# kirschmann-adsr.net
KiCad netlist of a schematic drawn in EAGLE
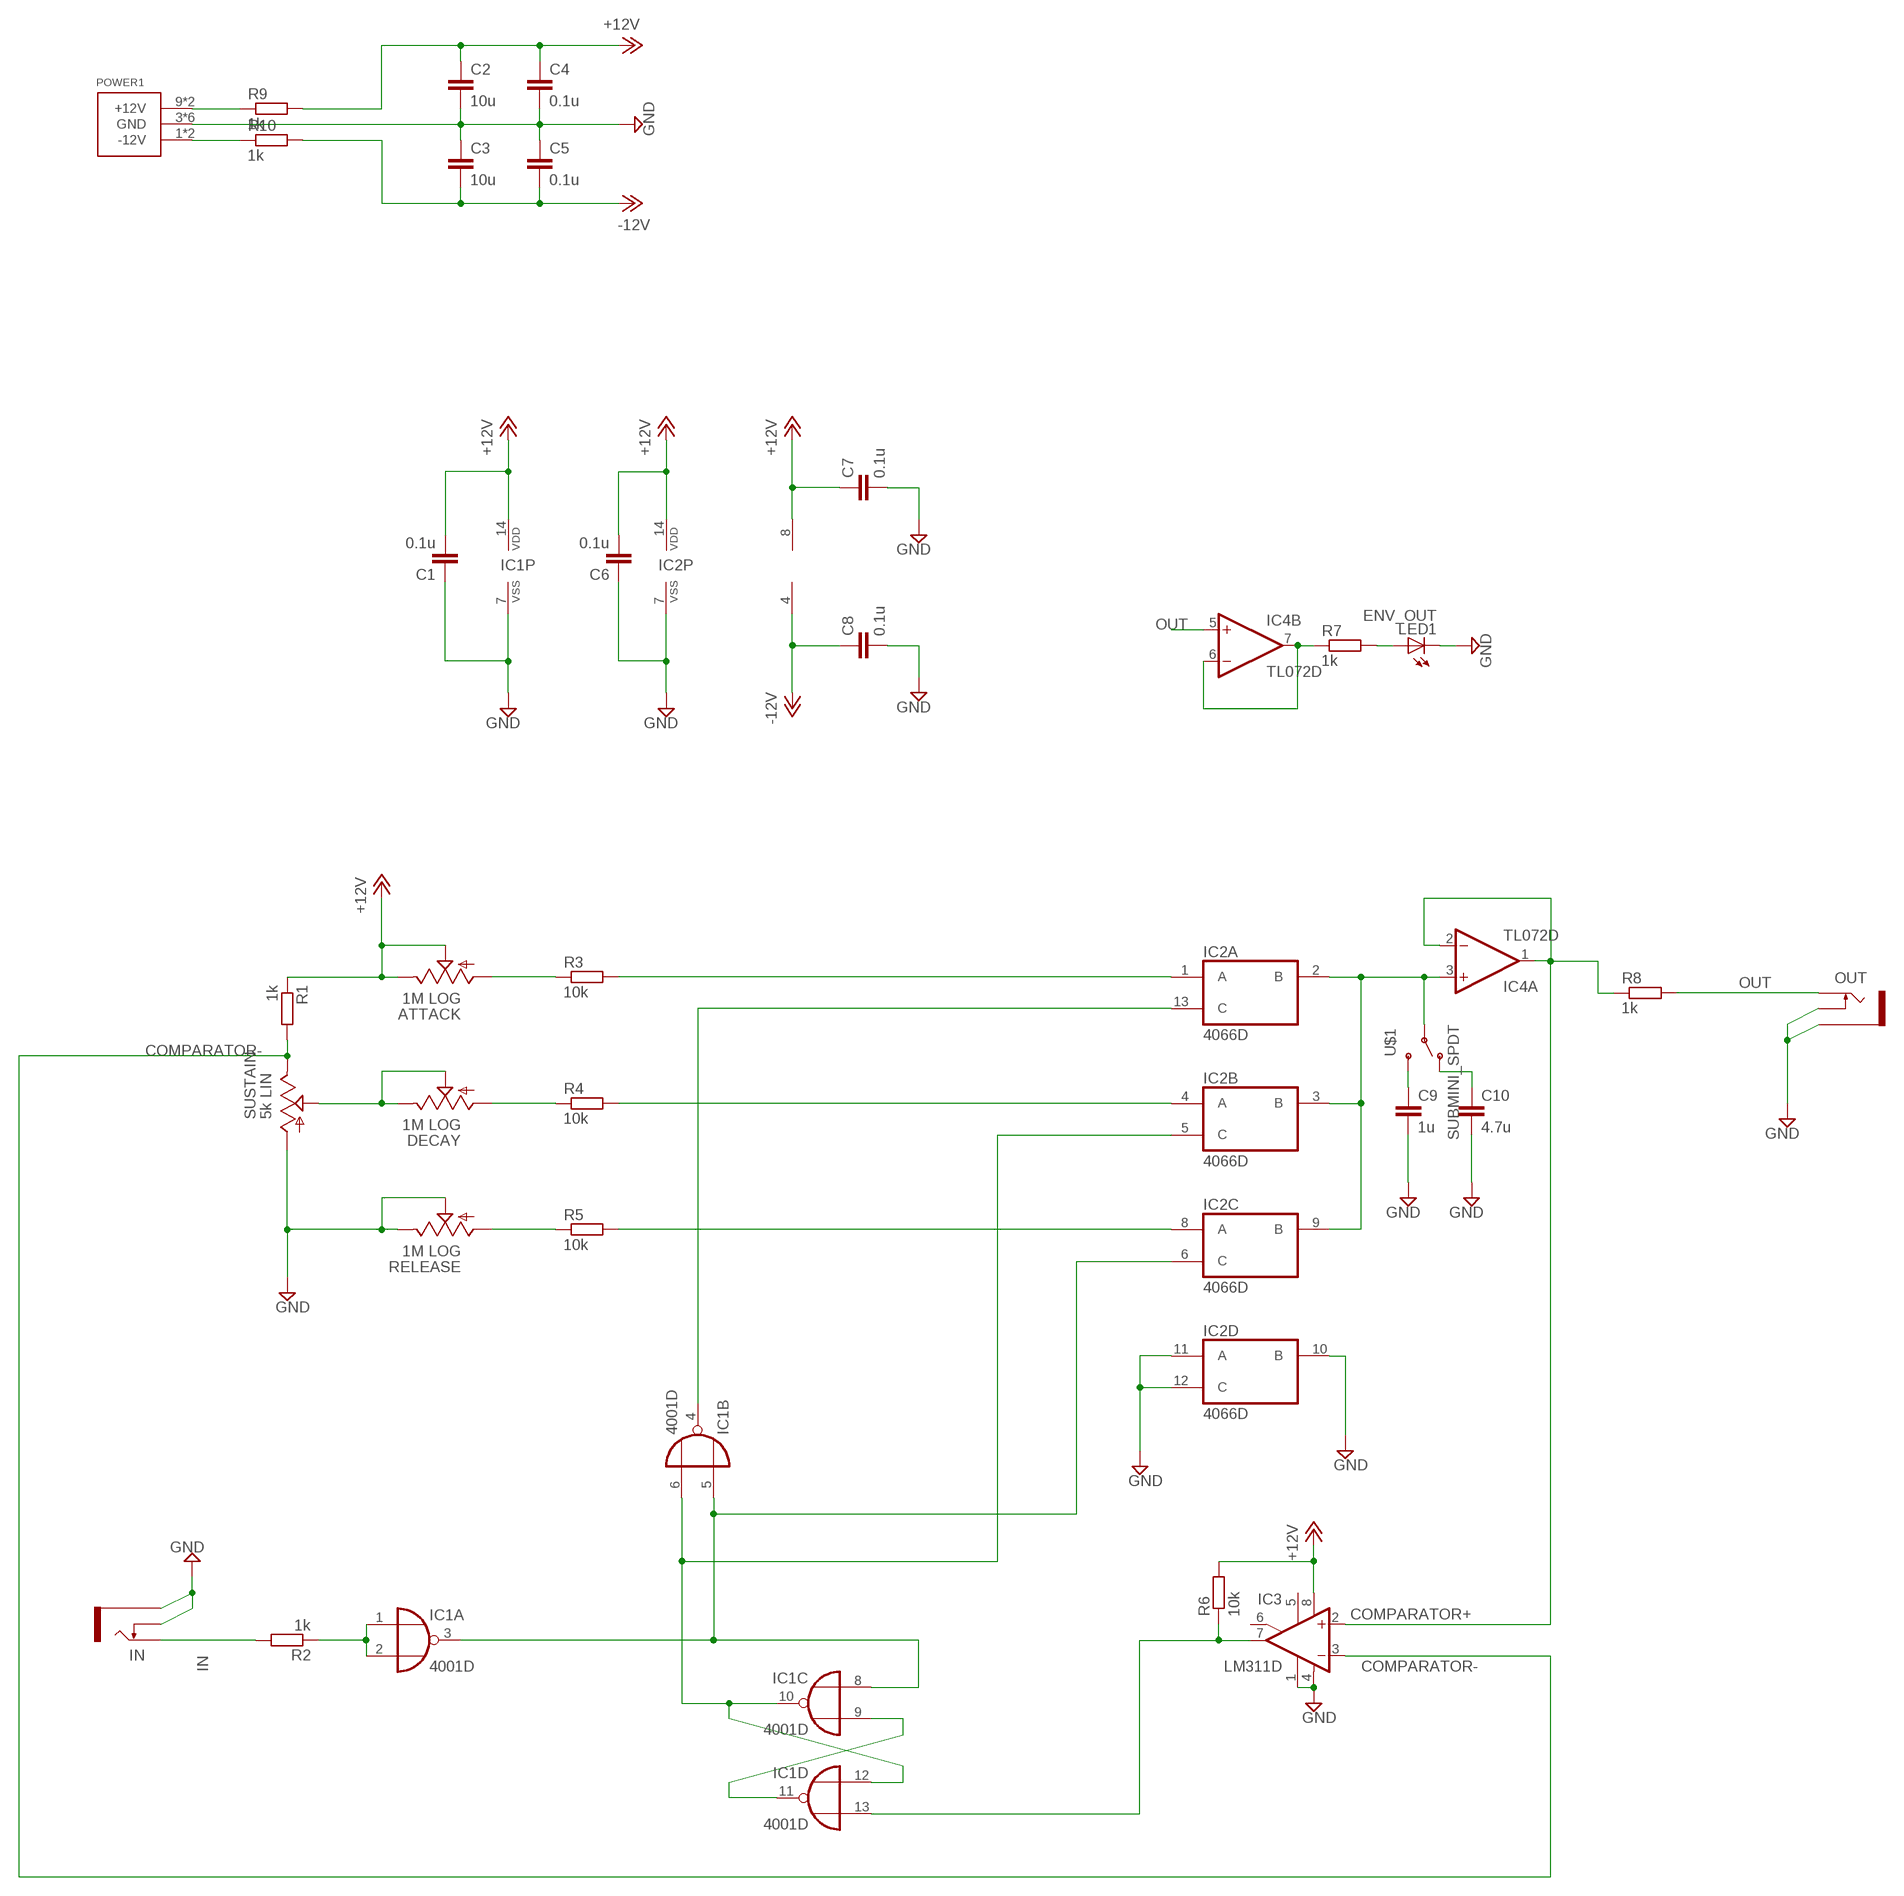
[diagram p0: schematic, sheet 1]

(export (version "E")
  (design (tool "Eeschema 10.0.6"))
  (components
    (comp (ref "ATTACK")
      (value "1M LOG")
      (footprint "eagle-import:9MM_SNAP-IN_POT")
      (libsource (lib "eagle-import") (part "9MM_SNAP-IN_POT_"))
    )
    (comp (ref "C1")
      (value "0.1u")
      (footprint "eagle-import:C0805")
      (libsource (lib "eagle-import") (part "C-EUC0805"))
    )
    (comp (ref "C2")
      (value "10u")
      (footprint "eagle-import:C0805")
      (libsource (lib "eagle-import") (part "C-EUC0805"))
    )
    (comp (ref "C3")
      (value "10u")
      (footprint "eagle-import:C0805")
      (libsource (lib "eagle-import") (part "C-EUC0805"))
    )
    (comp (ref "C4")
      (value "0.1u")
      (footprint "eagle-import:C0805")
      (libsource (lib "eagle-import") (part "C-EUC0805"))
    )
    (comp (ref "C5")
      (value "0.1u")
      (footprint "eagle-import:C0805")
      (libsource (lib "eagle-import") (part "C-EUC0805"))
    )
    (comp (ref "C6")
      (value "0.1u")
      (footprint "eagle-import:C0805")
      (libsource (lib "eagle-import") (part "C-EUC0805"))
    )
    (comp (ref "C7")
      (value "0.1u")
      (footprint "eagle-import:C0805")
      (libsource (lib "eagle-import") (part "C-EUC0805"))
    )
    (comp (ref "C8")
      (value "0.1u")
      (footprint "eagle-import:C0805")
      (libsource (lib "eagle-import") (part "C-EUC0805"))
    )
    (comp (ref "C9")
      (value "1u")
      (footprint "eagle-import:C0805")
      (libsource (lib "eagle-import") (part "C-EUC0805"))
    )
    (comp (ref "C10")
      (value "4.7u")
      (footprint "eagle-import:C0805")
      (libsource (lib "eagle-import") (part "C-EUC0805"))
    )
    (comp (ref "DECAY")
      (value "1M LOG")
      (footprint "eagle-import:9MM_SNAP-IN_POT")
      (libsource (lib "eagle-import") (part "9MM_SNAP-IN_POT_"))
    )
    (comp (ref "IC1")
      (value "4001D")
      (footprint "eagle-import:SO14")
      (libsource (lib "eagle-import") (part "4001D"))
    )
    (comp (ref "IC2")
      (value "4066D")
      (footprint "eagle-import:SO14")
      (libsource (lib "eagle-import") (part "4066D"))
    )
    (comp (ref "IC3")
      (value "LM311D")
      (footprint "eagle-import:SO08")
      (libsource (lib "eagle-import") (part "LM311D"))
    )
    (comp (ref "IC4")
      (value "TL072D")
      (footprint "eagle-import:SO08")
      (libsource (lib "eagle-import") (part "TL072D"))
    )
    (comp (ref "IN")
      (value "THONKICONNNEW")
      (footprint "eagle-import:WQP-PJ301M-12_JACK")
      (libsource (lib "eagle-import") (part "THONKICONNNEW"))
    )
    (comp (ref "LED1")
      (value "ENV_OUT")
      (footprint "eagle-import:LED3MM")
      (libsource (lib "eagle-import") (part "LED3MM"))
    )
    (comp (ref "OUT")
      (value "THONKICONNNEW")
      (footprint "eagle-import:WQP-PJ301M-12_JACK")
      (libsource (lib "eagle-import") (part "THONKICONNNEW"))
    )
    (comp (ref "POWER1")
      (value "POWER_SIMPLE10")
      (footprint "eagle-import:POWER_10")
      (libsource (lib "eagle-import") (part "POWER_SIMPLE10"))
    )
    (comp (ref "R1")
      (value "1k")
      (footprint "eagle-import:R0805")
      (libsource (lib "eagle-import") (part "R-EU_R0805"))
    )
    (comp (ref "R2")
      (value "1k")
      (footprint "eagle-import:R0805")
      (libsource (lib "eagle-import") (part "R-EU_R0805"))
    )
    (comp (ref "R3")
      (value "10k")
      (footprint "eagle-import:R0805")
      (libsource (lib "eagle-import") (part "R-EU_R0805"))
    )
    (comp (ref "R4")
      (value "10k")
      (footprint "eagle-import:R0805")
      (libsource (lib "eagle-import") (part "R-EU_R0805"))
    )
    (comp (ref "R5")
      (value "10k")
      (footprint "eagle-import:R0805")
      (libsource (lib "eagle-import") (part "R-EU_R0805"))
    )
    (comp (ref "R6")
      (value "10k")
      (footprint "eagle-import:R0805")
      (libsource (lib "eagle-import") (part "R-EU_R0805"))
    )
    (comp (ref "R7")
      (value "1k")
      (footprint "eagle-import:R0805")
      (libsource (lib "eagle-import") (part "R-EU_R0805"))
    )
    (comp (ref "R8")
      (value "1k")
      (footprint "eagle-import:R0805")
      (libsource (lib "eagle-import") (part "R-EU_R0805"))
    )
    (comp (ref "R9")
      (value "1k")
      (footprint "eagle-import:R0805")
      (libsource (lib "eagle-import") (part "R-EU_R0805"))
    )
    (comp (ref "R10")
      (value "1k")
      (footprint "eagle-import:R0805")
      (libsource (lib "eagle-import") (part "R-EU_R0805"))
    )
    (comp (ref "RELEASE")
      (value "1M LOG")
      (footprint "eagle-import:9MM_SNAP-IN_POT")
      (libsource (lib "eagle-import") (part "9MM_SNAP-IN_POT_"))
    )
    (comp (ref "SUSTAIN")
      (value "5k LIN")
      (footprint "eagle-import:9MM_SNAP-IN_POT")
      (libsource (lib "eagle-import") (part "9MM_SNAP-IN_POT_"))
    )
    (comp (ref "U$1")
      (value "SUBMINI_SPDT")
      (footprint "eagle-import:SUBMINI_TOGGLE")
      (libsource (lib "eagle-import") (part "SUBMINI_SPDT"))
    )
  )
  (nets
    (net (code "1") (name "+12V") (class "Default")
      (node (ref "ATTACK") (pin "2") (pinfunction "S_2") (pintype "passive"))
      (node (ref "ATTACK") (pin "3") (pinfunction "E_3") (pintype "passive"))
      (node (ref "C1") (pin "2") (pinfunction "2_2") (pintype "passive"))
      (node (ref "C2") (pin "1") (pinfunction "1_1") (pintype "passive"))
      (node (ref "C4") (pin "1") (pinfunction "1_1") (pintype "passive"))
      (node (ref "C6") (pin "2") (pinfunction "2_2") (pintype "passive"))
      (node (ref "C7") (pin "1") (pinfunction "1_1") (pintype "passive"))
      (node (ref "IC1") (pin "14") (pinfunction "VDD_14") (pintype "power_in"))
      (node (ref "IC2") (pin "14") (pinfunction "VDD_14") (pintype "power_in"))
      (node (ref "IC3") (pin "8") (pinfunction "V+_8") (pintype "power_in"))
      (node (ref "IC4") (pin "8") (pinfunction "V+_8") (pintype "power_in"))
      (node (ref "R1") (pin "1") (pinfunction "1_1") (pintype "passive"))
      (node (ref "R6") (pin "2") (pinfunction "2_2") (pintype "passive"))
      (node (ref "R9") (pin "2") (pinfunction "2_2") (pintype "passive"))
    )
    (net (code "2") (name "-12V") (class "Default")
      (node (ref "C3") (pin "2") (pinfunction "2_2") (pintype "passive"))
      (node (ref "C5") (pin "2") (pinfunction "2_2") (pintype "passive"))
      (node (ref "C8") (pin "1") (pinfunction "1_1") (pintype "passive"))
      (node (ref "IC4") (pin "4") (pinfunction "V-_4") (pintype "power_in"))
      (node (ref "R10") (pin "2") (pinfunction "2_2") (pintype "passive"))
    )
    (net (code "3") (name "/COMPARATOR+") (class "Default")
      (node (ref "IC3") (pin "2") (pinfunction "+IN_2") (pintype "input"))
      (node (ref "IC4") (pin "1") (pinfunction "OUT_1") (pintype "output"))
      (node (ref "IC4") (pin "2") (pinfunction "-IN_2") (pintype "input"))
      (node (ref "R8") (pin "1") (pinfunction "1_1") (pintype "passive"))
    )
    (net (code "4") (name "/COMPARATOR-") (class "Default")
      (node (ref "IC3") (pin "3") (pinfunction "-IN_3") (pintype "input"))
      (node (ref "R1") (pin "2") (pinfunction "2_2") (pintype "passive"))
      (node (ref "SUSTAIN") (pin "3") (pinfunction "E_3") (pintype "passive"))
    )
    (net (code "5") (name "/IN") (class "Default")
      (node (ref "IN") (pin "P$1_TIP") (pinfunction "TIP_P$1_TIP") (pintype "passive"))
      (node (ref "R2") (pin "2") (pinfunction "2_2") (pintype "passive"))
    )
    (net (code "6") (name "/OUT") (class "Default")
      (node (ref "IC4") (pin "5") (pinfunction "+IN_5") (pintype "input"))
      (node (ref "OUT") (pin "P$1_TIP") (pinfunction "TIP_P$1_TIP") (pintype "passive"))
      (node (ref "R8") (pin "2") (pinfunction "2_2") (pintype "passive"))
    )
    (net (code "7") (name "GND") (class "Default")
      (node (ref "C1") (pin "1") (pinfunction "1_1") (pintype "passive"))
      (node (ref "C10") (pin "2") (pinfunction "2_2") (pintype "passive"))
      (node (ref "C2") (pin "2") (pinfunction "2_2") (pintype "passive"))
      (node (ref "C3") (pin "1") (pinfunction "1_1") (pintype "passive"))
      (node (ref "C4") (pin "2") (pinfunction "2_2") (pintype "passive"))
      (node (ref "C5") (pin "1") (pinfunction "1_1") (pintype "passive"))
      (node (ref "C6") (pin "1") (pinfunction "1_1") (pintype "passive"))
      (node (ref "C7") (pin "2") (pinfunction "2_2") (pintype "passive"))
      (node (ref "C8") (pin "2") (pinfunction "2_2") (pintype "passive"))
      (node (ref "C9") (pin "2") (pinfunction "2_2") (pintype "passive"))
      (node (ref "IC1") (pin "7") (pinfunction "VSS_7") (pintype "power_in"))
      (node (ref "IC2") (pin "10") (pinfunction "B_10") (pintype "tri_state"))
      (node (ref "IC2") (pin "11") (pinfunction "A_11") (pintype "tri_state"))
      (node (ref "IC2") (pin "12") (pinfunction "C_12") (pintype "input"))
      (node (ref "IC2") (pin "7") (pinfunction "VSS_7") (pintype "power_in"))
      (node (ref "IC3") (pin "1") (pinfunction "GND_1") (pintype "passive"))
      (node (ref "IC3") (pin "4") (pinfunction "V-_4") (pintype "power_in"))
      (node (ref "IN") (pin "P$2_SWITCH") (pinfunction "SWITCH_P$2_SWITCH") (pintype "passive"))
      (node (ref "IN") (pin "P$3_SLEEVE") (pinfunction "SLEEVE_P$3_SLEEVE") (pintype "passive"))
      (node (ref "LED1") (pin "K") (pinfunction "C_K") (pintype "passive"))
      (node (ref "OUT") (pin "P$2_SWITCH") (pinfunction "SWITCH_P$2_SWITCH") (pintype "passive"))
      (node (ref "OUT") (pin "P$3_SLEEVE") (pinfunction "SLEEVE_P$3_SLEEVE") (pintype "passive"))
      (node (ref "POWER1") (pin "3") (pinfunction "GND_3") (pintype "bidirectional"))
      (node (ref "POWER1") (pin "4") (pinfunction "GND_4") (pintype "bidirectional"))
      (node (ref "POWER1") (pin "5") (pinfunction "GND_5") (pintype "bidirectional"))
      (node (ref "POWER1") (pin "6") (pinfunction "GND_6") (pintype "bidirectional"))
      (node (ref "POWER1") (pin "7") (pinfunction "GND_7") (pintype "bidirectional"))
      (node (ref "POWER1") (pin "8") (pinfunction "GND_8") (pintype "bidirectional"))
      (node (ref "RELEASE") (pin "2") (pinfunction "S_2") (pintype "passive"))
      (node (ref "RELEASE") (pin "3") (pinfunction "E_3") (pintype "passive"))
      (node (ref "SUSTAIN") (pin "1") (pinfunction "A_1") (pintype "passive"))
    )
    (net (code "8") (name "Net-(ATTACK-A)") (class "Default")
      (node (ref "ATTACK") (pin "1") (pinfunction "A_1") (pintype "passive"))
      (node (ref "R3") (pin "1") (pinfunction "1_1") (pintype "passive"))
    )
    (net (code "9") (name "Net-(DECAY-A)") (class "Default")
      (node (ref "DECAY") (pin "1") (pinfunction "A_1") (pintype "passive"))
      (node (ref "R4") (pin "1") (pinfunction "1_1") (pintype "passive"))
    )
    (net (code "10") (name "Net-(DECAY-E)") (class "Default")
      (node (ref "DECAY") (pin "2") (pinfunction "S_2") (pintype "passive"))
      (node (ref "DECAY") (pin "3") (pinfunction "E_3") (pintype "passive"))
      (node (ref "SUSTAIN") (pin "2") (pinfunction "S_2") (pintype "passive"))
    )
    (net (code "11") (name "Net-(IC1A-I0)") (class "Default")
      (node (ref "IC1") (pin "1") (pinfunction "I0_1") (pintype "input"))
      (node (ref "IC1") (pin "2") (pinfunction "I1_2") (pintype "input"))
      (node (ref "R2") (pin "1") (pinfunction "1_1") (pintype "passive"))
    )
    (net (code "12") (name "Net-(IC1A-O)") (class "Default")
      (node (ref "IC1") (pin "3") (pinfunction "O_3") (pintype "output"))
      (node (ref "IC1") (pin "5") (pinfunction "I0_5") (pintype "input"))
      (node (ref "IC1") (pin "8") (pinfunction "I0_8") (pintype "input"))
      (node (ref "IC2") (pin "6") (pinfunction "C_6") (pintype "input"))
    )
    (net (code "13") (name "Net-(IC1B-I1)") (class "Default")
      (node (ref "IC1") (pin "10") (pinfunction "O_10") (pintype "output"))
      (node (ref "IC1") (pin "12") (pinfunction "I0_12") (pintype "input"))
      (node (ref "IC1") (pin "6") (pinfunction "I1_6") (pintype "input"))
      (node (ref "IC2") (pin "5") (pinfunction "C_5") (pintype "input"))
    )
    (net (code "14") (name "Net-(IC1B-O)") (class "Default")
      (node (ref "IC1") (pin "4") (pinfunction "O_4") (pintype "output"))
      (node (ref "IC2") (pin "13") (pinfunction "C_13") (pintype "input"))
    )
    (net (code "15") (name "Net-(IC1C-I1)") (class "Default")
      (node (ref "IC1") (pin "11") (pinfunction "O_11") (pintype "output"))
      (node (ref "IC1") (pin "9") (pinfunction "I1_9") (pintype "input"))
    )
    (net (code "16") (name "Net-(IC1D-I1)") (class "Default")
      (node (ref "IC1") (pin "13") (pinfunction "I1_13") (pintype "input"))
      (node (ref "IC3") (pin "7") (pinfunction "OUT_7") (pintype "output"))
      (node (ref "R6") (pin "1") (pinfunction "1_1") (pintype "passive"))
    )
    (net (code "17") (name "Net-(IC2A-A)") (class "Default")
      (node (ref "IC2") (pin "1") (pinfunction "A_1") (pintype "tri_state"))
      (node (ref "R3") (pin "2") (pinfunction "2_2") (pintype "passive"))
    )
    (net (code "18") (name "Net-(IC2A-B)") (class "Default")
      (node (ref "IC2") (pin "2") (pinfunction "B_2") (pintype "tri_state"))
      (node (ref "IC2") (pin "3") (pinfunction "B_3") (pintype "tri_state"))
      (node (ref "IC2") (pin "9") (pinfunction "B_9") (pintype "tri_state"))
      (node (ref "IC4") (pin "3") (pinfunction "+IN_3") (pintype "input"))
      (node (ref "U$1") (pin "COM") (pinfunction "COMMON_COM") (pintype "passive"))
    )
    (net (code "19") (name "Net-(IC2B-A)") (class "Default")
      (node (ref "IC2") (pin "4") (pinfunction "A_4") (pintype "tri_state"))
      (node (ref "R4") (pin "2") (pinfunction "2_2") (pintype "passive"))
    )
    (net (code "20") (name "Net-(IC2C-A)") (class "Default")
      (node (ref "IC2") (pin "8") (pinfunction "A_8") (pintype "tri_state"))
      (node (ref "R5") (pin "2") (pinfunction "2_2") (pintype "passive"))
    )
    (net (code "21") (name "Net-(IC4B--IN)") (class "Default")
      (node (ref "IC4") (pin "6") (pinfunction "-IN_6") (pintype "input"))
      (node (ref "IC4") (pin "7") (pinfunction "OUT_7") (pintype "output"))
      (node (ref "R7") (pin "1") (pinfunction "1_1") (pintype "passive"))
    )
    (net (code "22") (name "Net-(LED1-PadA)") (class "Default")
      (node (ref "LED1") (pin "A") (pinfunction "A_A") (pintype "passive"))
      (node (ref "R7") (pin "2") (pinfunction "2_2") (pintype "passive"))
    )
    (net (code "23") (name "Net-(POWER1-+12V-Pad10)") (class "Default")
      (node (ref "POWER1") (pin "10") (pinfunction "+12V_10") (pintype "bidirectional"))
      (node (ref "POWER1") (pin "9") (pinfunction "+12V_9") (pintype "bidirectional"))
      (node (ref "R9") (pin "1") (pinfunction "1_1") (pintype "passive"))
    )
    (net (code "24") (name "Net-(POWER1--12V-Pad1)") (class "Default")
      (node (ref "POWER1") (pin "1") (pinfunction "-12V_1") (pintype "bidirectional"))
      (node (ref "POWER1") (pin "2") (pinfunction "-12V_2") (pintype "bidirectional"))
      (node (ref "R10") (pin "1") (pinfunction "1_1") (pintype "passive"))
    )
    (net (code "25") (name "Net-(RELEASE-A)") (class "Default")
      (node (ref "R5") (pin "1") (pinfunction "1_1") (pintype "passive"))
      (node (ref "RELEASE") (pin "1") (pinfunction "A_1") (pintype "passive"))
    )
    (net (code "26") (name "Net-(U$1-O)") (class "Default")
      (node (ref "C10") (pin "1") (pinfunction "1_1") (pintype "passive"))
      (node (ref "U$1") (pin "1") (pinfunction "O_1") (pintype "passive"))
    )
    (net (code "27") (name "Net-(U$1-S)") (class "Default")
      (node (ref "C9") (pin "1") (pinfunction "1_1") (pintype "passive"))
      (node (ref "U$1") (pin "3") (pinfunction "S_3") (pintype "passive"))
    )
    (net (code "28") (name "unconnected-(IC3-ON-Pad5)") (class "Default")
      (node (ref "IC3") (pin "5") (pinfunction "ON_5") (pintype "passive"))
    )
    (net (code "29") (name "unconnected-(IC3-ON{slash}STR-Pad6)") (class "Default")
      (node (ref "IC3") (pin "6") (pinfunction "ON/STR_6") (pintype "passive"))
    )
  )
)
